# ORing_Controller_and_FETs.net
KiCad netlist of a schematic drawn in Altium Designer
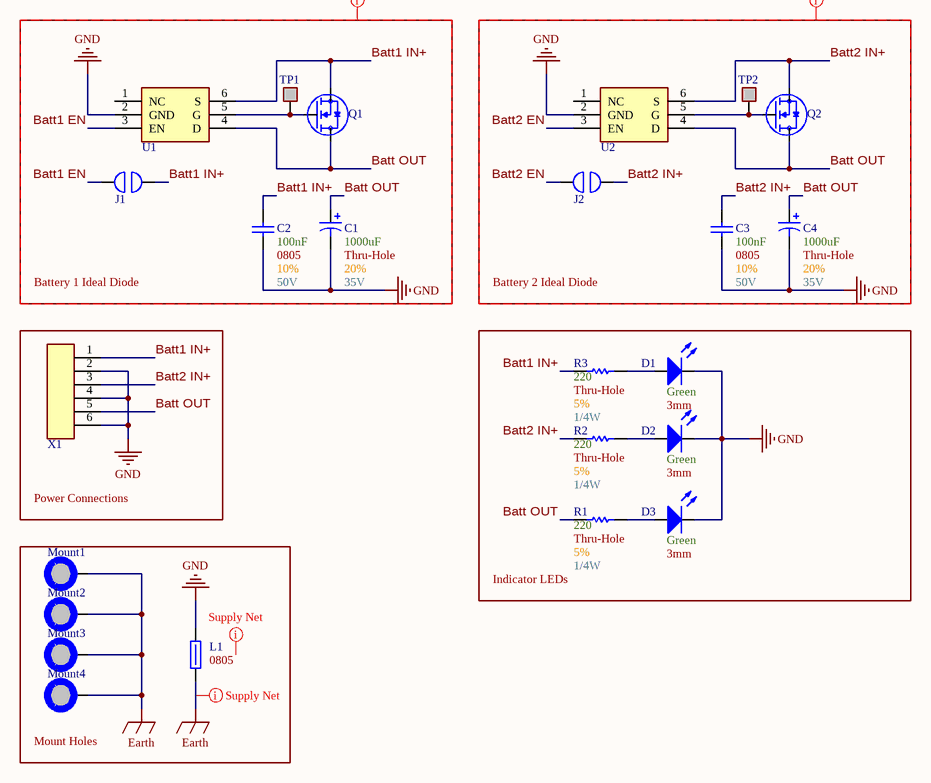
[diagram p0: ORing Controller and FETs.SchDoc]

(export (version "E")
  (design (tool "Eeschema 10.0.6"))
  (components
    (comp (ref "C1")
      (value "[Cap] Thru-Hole 1000uF 20% 35V")
      (footprint "[Cap] Thru-Hole Polarized 10mm")
      (description "35PK1000MEFC10X20")
      (fields
        (field (name "MAX VOLTAGE") "35V")
        (field (name "SIZE PACKAGE") "Thru-Hole")
        (field (name "TOLERANCE") "20%")
        (field (name "CAPACITANCE") "1000uF")
      )
      (libsource (lib "Capacitors") (part "[Cap] Thru-Hole 1000uF 20% 35V"))
    )
    (comp (ref "C2")
      (value "[Cap] 0805 0.1uF 10% 50V")
      (footprint "[Cap] SMD 0805")
      (description "CL21B104KBCNNNC")
      (fields
        (field (name "MAX VOLTAGE") "50V")
        (field (name "SIZE PACKAGE") "0805")
        (field (name "TOLERANCE") "10%")
        (field (name "CAPACITANCE") "100nF")
      )
      (libsource (lib "Capacitors") (part "[Cap] 0805 0.1uF 10% 50V"))
    )
    (comp (ref "C3")
      (value "[Cap] 0805 0.1uF 10% 50V")
      (footprint "[Cap] SMD 0805")
      (description "CL21B104KBCNNNC")
      (fields
        (field (name "MAX VOLTAGE") "50V")
        (field (name "SIZE PACKAGE") "0805")
        (field (name "TOLERANCE") "10%")
        (field (name "CAPACITANCE") "100nF")
      )
      (libsource (lib "Capacitors") (part "[Cap] 0805 0.1uF 10% 50V"))
    )
    (comp (ref "C4")
      (value "[Cap] Thru-Hole 1000uF 20% 35V")
      (footprint "[Cap] Thru-Hole Polarized 10mm")
      (description "35PK1000MEFC10X20")
      (fields
        (field (name "MAX VOLTAGE") "35V")
        (field (name "SIZE PACKAGE") "Thru-Hole")
        (field (name "TOLERANCE") "20%")
        (field (name "CAPACITANCE") "1000uF")
      )
      (libsource (lib "Capacitors") (part "[Cap] Thru-Hole 1000uF 20% 35V"))
    )
    (comp (ref "D1")
      (value "[LED] Thru-Hole 3mm Green")
      (footprint "[LED] Thru-Hole 3mm")
      (description "151031VS06000")
      (fields (field (name "COLOR") "Green") (field (name "LENS DIAMETER") "3mm"))
      (libsource (lib "LEDs") (part "[LED] Thru-Hole 3mm Green"))
    )
    (comp (ref "D2")
      (value "[LED] Thru-Hole 3mm Green")
      (footprint "[LED] Thru-Hole 3mm")
      (description "151031VS06000")
      (fields (field (name "COLOR") "Green") (field (name "LENS DIAMETER") "3mm"))
      (libsource (lib "LEDs") (part "[LED] Thru-Hole 3mm Green"))
    )
    (comp (ref "D3")
      (value "[LED] Thru-Hole 3mm Green")
      (footprint "[LED] Thru-Hole 3mm")
      (description "151031VS06000")
      (fields (field (name "COLOR") "Green") (field (name "LENS DIAMETER") "3mm"))
      (libsource (lib "LEDs") (part "[LED] Thru-Hole 3mm Green"))
    )
    (comp (ref "J1")
      (value "[Jumper] Thru-Hole 2pin")
      (footprint "[Jumper] Thru-Hole 2pin")
      (libsource (lib "Misc Components") (part "[Jumper] Thru-Hole 2pin"))
    )
    (comp (ref "J2")
      (value "[Jumper] Thru-Hole 2pin")
      (footprint "[Jumper] Thru-Hole 2pin")
      (libsource (lib "Misc Components") (part "[Jumper] Thru-Hole 2pin"))
    )
    (comp (ref "L1")
      (value "652-MH2029-300Y")
      (footprint "[Ferrite] SMD 0805")
      (fields (field (name "SIZE PACKAGE") "0805"))
      (libsource (lib "Ferrite Beads") (part "[Ferrite] SMD 0805 3A 30ohm"))
    )
    (comp (ref "Mount1")
      (value "M3 Mount Hole")
      (footprint "[Mount] M3 Mount Hole")
      (description "Place at least 4.5mm from board edge. Plated.")
      (libsource (lib "Misc Components") (part "[Mount] M3 Mount Hole"))
    )
    (comp (ref "Mount2")
      (value "M3 Mount Hole")
      (footprint "[Mount] M3 Mount Hole")
      (description "Place at least 4.5mm from board edge. Plated.")
      (libsource (lib "Misc Components") (part "[Mount] M3 Mount Hole"))
    )
    (comp (ref "Mount3")
      (value "M3 Mount Hole")
      (footprint "[Mount] M3 Mount Hole")
      (description "Place at least 4.5mm from board edge. Plated.")
      (libsource (lib "Misc Components") (part "[Mount] M3 Mount Hole"))
    )
    (comp (ref "Mount4")
      (value "M3 Mount Hole")
      (footprint "[Mount] M3 Mount Hole")
      (description "Place at least 4.5mm from board edge. Plated.")
      (libsource (lib "Misc Components") (part "[Mount] M3 Mount Hole"))
    )
    (comp (ref "Q1")
      (value "NMOS")
      (footprint "[NMOS] Thru-Hole 40V 200A")
      (description "CSD18510KCS")
      (libsource (lib "Transistors") (part "[NMOS] Thru-Hole 40V 200A"))
    )
    (comp (ref "Q2")
      (value "NMOS")
      (footprint "[NMOS] Thru-Hole 40V 200A")
      (description "CSD18510KCS")
      (libsource (lib "Transistors") (part "[NMOS] Thru-Hole 40V 200A"))
    )
    (comp (ref "R1")
      (value "[220] Thru-Hole 5% 1/4W")
      (footprint "[Res] Thru-Hole 1/4W")
      (description "CFR-25JR-52-220R")
      (fields
        (field (name "SIZE PACKAGE") "Thru-Hole")
        (field (name "WATTAGE") "1/4W")
        (field (name "TOLERANCE") "5%")
        (field (name "RESISTANCE") "220")
      )
      (libsource (lib "Resistors") (part "[220] Thru-Hole 5% 1/4W"))
    )
    (comp (ref "R2")
      (value "[220] Thru-Hole 5% 1/4W")
      (footprint "[Res] Thru-Hole 1/4W")
      (description "CFR-25JR-52-220R")
      (fields
        (field (name "SIZE PACKAGE") "Thru-Hole")
        (field (name "WATTAGE") "1/4W")
        (field (name "TOLERANCE") "5%")
        (field (name "RESISTANCE") "220")
      )
      (libsource (lib "Resistors") (part "[220] Thru-Hole 5% 1/4W"))
    )
    (comp (ref "R3")
      (value "[220] Thru-Hole 5% 1/4W")
      (footprint "[Res] Thru-Hole 1/4W")
      (description "CFR-25JR-52-220R")
      (fields
        (field (name "SIZE PACKAGE") "Thru-Hole")
        (field (name "WATTAGE") "1/4W")
        (field (name "TOLERANCE") "5%")
        (field (name "RESISTANCE") "220")
      )
      (libsource (lib "Resistors") (part "[220] Thru-Hole 5% 1/4W"))
    )
    (comp (ref "TP1")
      (value "[THM] Thru-Hole")
      (footprint "[THM] White")
      (description "5012")
      (libsource (lib "Test Points") (part "[THM] Thru-Hole"))
    )
    (comp (ref "TP2")
      (value "[THM] Thru-Hole")
      (footprint "[THM] White")
      (description "5012")
      (libsource (lib "Test Points") (part "[THM] Thru-Hole"))
    )
    (comp (ref "U1")
      (value "[ORing] NMOS Controller")
      (footprint "[ORing] NMOS Controller")
      (description "NCV68061SNAIT1G")
      (libsource (lib "ICs") (part "[ORing] NMOS Controller"))
    )
    (comp (ref "U2")
      (value "[ORing] NMOS Controller")
      (footprint "[ORing] NMOS Controller")
      (description "NCV68061SNAIT1G")
      (libsource (lib "ICs") (part "[ORing] NMOS Controller"))
    )
    (comp (ref "X1")
      (value "6pin Screw Terminal")
      (footprint "[Screw Terminal] 6pin 5mm")
      (description "TB002-500-06BE")
      (libsource (lib "Connectors") (part "[Screw Terminal] 6pin"))
    )
  )
  (nets
    (net (code "1") (name "/Batt OUT") (class "Default")
      (node (ref "C1") (pin "1") (pinfunction "1_1") (pintype "passive"))
      (node (ref "C4") (pin "1") (pinfunction "1_1") (pintype "passive"))
      (node (ref "Q1") (pin "3") (pinfunction "Drain_3") (pintype "passive"))
      (node (ref "Q2") (pin "3") (pinfunction "Drain_3") (pintype "passive"))
      (node (ref "R1") (pin "1") (pinfunction "1_1") (pintype "passive"))
      (node (ref "U1") (pin "4") (pinfunction "D_4") (pintype "passive"))
      (node (ref "U2") (pin "4") (pinfunction "D_4") (pintype "passive"))
      (node (ref "X1") (pin "5") (pintype "power_in"))
    )
    (net (code "2") (name "/Batt1 EN") (class "Default")
      (node (ref "J1") (pin "1") (pintype "passive"))
      (node (ref "U1") (pin "3") (pinfunction "EN_3") (pintype "passive"))
    )
    (net (code "3") (name "/Batt1 IN+") (class "Default")
      (node (ref "C2") (pin "1") (pinfunction "1_1") (pintype "passive"))
      (node (ref "J1") (pin "2") (pintype "passive"))
      (node (ref "Q1") (pin "2") (pinfunction "Source_2") (pintype "passive"))
      (node (ref "R3") (pin "1") (pinfunction "1_1") (pintype "passive"))
      (node (ref "U1") (pin "6") (pinfunction "S_6") (pintype "passive"))
      (node (ref "X1") (pin "1") (pintype "power_in"))
    )
    (net (code "4") (name "/Batt2 EN") (class "Default")
      (node (ref "J2") (pin "1") (pintype "passive"))
      (node (ref "U2") (pin "3") (pinfunction "EN_3") (pintype "passive"))
    )
    (net (code "5") (name "/Batt2 IN+") (class "Default")
      (node (ref "C3") (pin "1") (pinfunction "1_1") (pintype "passive"))
      (node (ref "J2") (pin "2") (pintype "passive"))
      (node (ref "Q2") (pin "2") (pinfunction "Source_2") (pintype "passive"))
      (node (ref "R2") (pin "1") (pinfunction "1_1") (pintype "passive"))
      (node (ref "U2") (pin "6") (pinfunction "S_6") (pintype "passive"))
      (node (ref "X1") (pin "3") (pintype "power_in"))
    )
    (net (code "6") (name "Earth") (class "Default")
      (node (ref "L1") (pin "1") (pinfunction "1_1") (pintype "passive"))
      (node (ref "Mount1") (pin "1") (pintype "power_in"))
      (node (ref "Mount2") (pin "1") (pintype "power_in"))
      (node (ref "Mount3") (pin "1") (pintype "power_in"))
      (node (ref "Mount4") (pin "1") (pintype "power_in"))
    )
    (net (code "7") (name "GND") (class "Default")
      (node (ref "C1") (pin "2") (pinfunction "2_2") (pintype "passive"))
      (node (ref "C2") (pin "2") (pinfunction "2_2") (pintype "passive"))
      (node (ref "C3") (pin "2") (pinfunction "2_2") (pintype "passive"))
      (node (ref "C4") (pin "2") (pinfunction "2_2") (pintype "passive"))
      (node (ref "D1") (pin "2") (pinfunction "Cathode_2") (pintype "passive"))
      (node (ref "D2") (pin "2") (pinfunction "Cathode_2") (pintype "passive"))
      (node (ref "D3") (pin "2") (pinfunction "Cathode_2") (pintype "passive"))
      (node (ref "L1") (pin "2") (pinfunction "2_2") (pintype "passive"))
      (node (ref "U1") (pin "2") (pinfunction "GND_2") (pintype "passive"))
      (node (ref "U2") (pin "2") (pinfunction "GND_2") (pintype "passive"))
      (node (ref "X1") (pin "2") (pintype "power_in"))
      (node (ref "X1") (pin "4") (pintype "power_in"))
      (node (ref "X1") (pin "6") (pintype "power_in"))
    )
    (net (code "8") (name "Net-(D1-Anode)") (class "Default")
      (node (ref "D1") (pin "1") (pinfunction "Anode_1") (pintype "passive"))
      (node (ref "R3") (pin "2") (pinfunction "2_2") (pintype "passive"))
    )
    (net (code "9") (name "Net-(D2-Anode)") (class "Default")
      (node (ref "D2") (pin "1") (pinfunction "Anode_1") (pintype "passive"))
      (node (ref "R2") (pin "2") (pinfunction "2_2") (pintype "passive"))
    )
    (net (code "10") (name "Net-(D3-Anode)") (class "Default")
      (node (ref "D3") (pin "1") (pinfunction "Anode_1") (pintype "passive"))
      (node (ref "R1") (pin "2") (pinfunction "2_2") (pintype "passive"))
    )
    (net (code "11") (name "Net-(Q1-Gate)") (class "Default")
      (node (ref "Q1") (pin "1") (pinfunction "Gate_1") (pintype "passive"))
      (node (ref "TP1") (pin "1") (pinfunction "1_1") (pintype "passive"))
      (node (ref "U1") (pin "5") (pinfunction "G_5") (pintype "passive"))
    )
    (net (code "12") (name "Net-(Q2-Gate)") (class "Default")
      (node (ref "Q2") (pin "1") (pinfunction "Gate_1") (pintype "passive"))
      (node (ref "TP2") (pin "1") (pinfunction "1_1") (pintype "passive"))
      (node (ref "U2") (pin "5") (pinfunction "G_5") (pintype "passive"))
    )
    (net (code "13") (name "unconnected-(U1-NC-Pad1)") (class "Default")
      (node (ref "U1") (pin "1") (pinfunction "NC_1") (pintype "passive"))
    )
    (net (code "14") (name "unconnected-(U2-NC-Pad1)") (class "Default")
      (node (ref "U2") (pin "1") (pinfunction "NC_1") (pintype "passive"))
    )
  )
)
